# Sheet1.net
KiCad netlist of a schematic drawn in Altium Designer
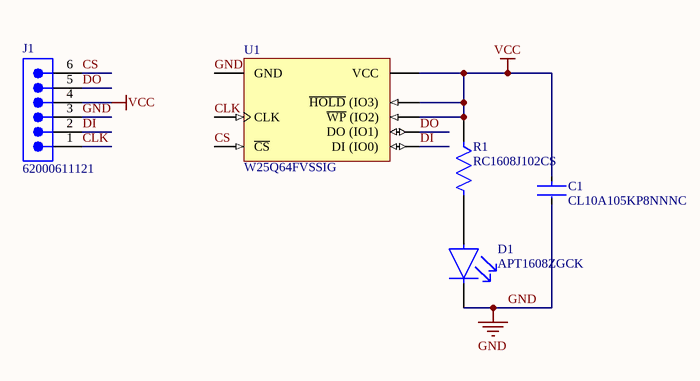
[diagram p0: Sheet1.SchDoc]

(export (version "E")
  (design (tool "Eeschema 10.0.6"))
  (components
    (comp (ref "C1")
      (value "CL10A105KP8NNNC")
      (footprint "FP-CL10-IPC_A")
      (description "Cap Ceramic 1uF 10V X5R ±10% Pad SMD 0603 +85°C T/R")
      (fields (field (name "VOLTAGE") "10V") (field (name "TOLERANCE") "10%"))
      (libsource (lib "CL10A105KP8NNNC") (part "CMP-13271-003399-1"))
    )
    (comp (ref "D1")
      (value "APT1608ZGCK")
      (footprint "FP-APT1608ZGCK-MFG")
      (description "LED GREEN CLEAR CHIP SMD")
      (libsource (lib "APT1608ZGCK") (part "CMP-44529-000024-1"))
    )
    (comp (ref "J1")
      (value "62000611121")
      (footprint "62000611121")
      (libsource (lib "62000611121") (part "CMP-1502-00960-3"))
    )
    (comp (ref "R1")
      (value "RC1608J102CS")
      (footprint "FP-RC1608-IPC_C")
      (description "Res Thick Film 0603 1kΩ 5% 0.1W ±100ppm/°C Molded SMD T/R")
      (fields (field (name "TOLERANCE") "5%"))
      (libsource (lib "RC1608J102CS") (part "CMP-13261-002301-1"))
    )
    (comp (ref "U1")
      (value "W25Q64FVSSIG")
      (footprint "WINB-SOIC-8_N")
      (fields (field (name "MANUFACTURER") "Winbond"))
      (libsource (lib "W25Q128FVSIG") (part "CMP-2000-05007-1"))
    )
  )
  (nets
    (net (code "1") (name "/CLK") (class "Default")
      (node (ref "J1") (pin "1") (pinfunction "1_1") (pintype "passive"))
      (node (ref "U1") (pin "6") (pinfunction "CLK_6") (pintype "input"))
    )
    (net (code "2") (name "/CS") (class "Default")
      (node (ref "J1") (pin "6") (pinfunction "6_6") (pintype "passive"))
      (node (ref "U1") (pin "1") (pinfunction "~{CS}_1") (pintype "input"))
    )
    (net (code "3") (name "/DI") (class "Default")
      (node (ref "J1") (pin "2") (pinfunction "2_2") (pintype "passive"))
      (node (ref "U1") (pin "5") (pinfunction "DI_(IO0)_5") (pintype "bidirectional"))
    )
    (net (code "4") (name "/DO") (class "Default")
      (node (ref "J1") (pin "5") (pinfunction "5_5") (pintype "passive"))
      (node (ref "U1") (pin "2") (pinfunction "DO_(IO1)_2") (pintype "bidirectional"))
    )
    (net (code "5") (name "GND") (class "Default")
      (node (ref "C1") (pin "2") (pinfunction "2_2") (pintype "passive"))
      (node (ref "D1") (pin "1") (pinfunction "C_1") (pintype "passive"))
      (node (ref "J1") (pin "3") (pinfunction "3_3") (pintype "passive"))
      (node (ref "U1") (pin "4") (pinfunction "GND_4") (pintype "power_in"))
    )
    (net (code "6") (name "Net-(D1-A)") (class "Default")
      (node (ref "D1") (pin "2") (pinfunction "A_2") (pintype "passive"))
      (node (ref "R1") (pin "2") (pinfunction "2_2") (pintype "passive"))
    )
    (net (code "7") (name "VCC") (class "Default")
      (node (ref "C1") (pin "1") (pinfunction "1_1") (pintype "passive"))
      (node (ref "J1") (pin "4") (pinfunction "4_4") (pintype "passive"))
      (node (ref "R1") (pin "1") (pinfunction "1_1") (pintype "passive"))
      (node (ref "U1") (pin "3") (pinfunction "~{WP}_(IO2)_3") (pintype "input"))
      (node (ref "U1") (pin "7") (pinfunction "~{HOLD}_(IO3)_7") (pintype "input"))
      (node (ref "U1") (pin "8") (pinfunction "VCC_8") (pintype "power_in"))
    )
  )
)
